# mcu_debug.net
KiCad netlist of a schematic drawn in Altium Designer
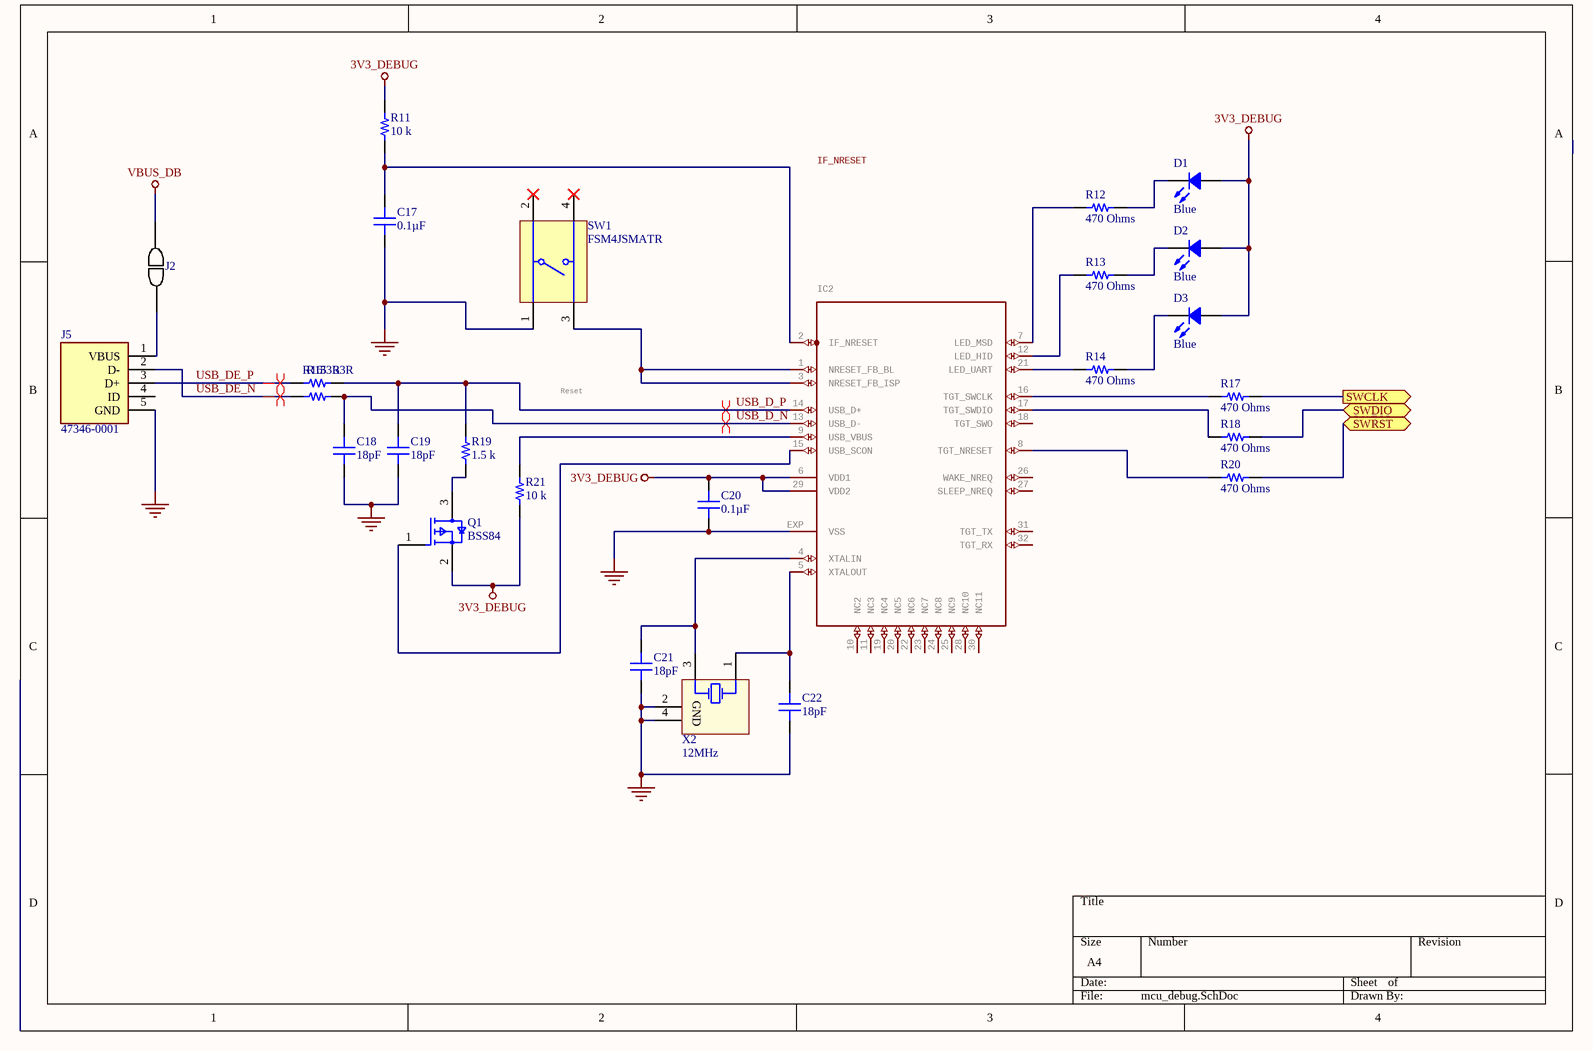
[diagram p0: mcu_debug.SchDoc]

(export (version "E")
  (design (tool "Eeschema 10.0.6"))
  (components
    (comp (ref "C17")
      (value "0.1µF")
      (footprint "CAP 0603_1608")
      (description "CAP CER 0.1UF 10V X7R 0603")
      (fields (field (name "PART NUMBER") "C0603T104K8RAC7867") (field (name "MANUFACTURER") "KEMET"))
      (libsource (lib "Celestial Altium Library - altium_library (2)") (part "Capacitor"))
    )
    (comp (ref "C18")
      (value "18pF")
      (footprint "CAP 0603_1608")
      (description "CAP CER 18PF 10V C0G/NP0 0603")
      (fields
        (field (name "PART NUMBER") "VJ0603A180FXQCW1BC")
        (field (name "MANUFACTURER") "Vishay Vitramon")
      )
      (libsource (lib "Celestial Altium Library - altium_library (2)") (part "Capacitor"))
    )
    (comp (ref "C19")
      (value "18pF")
      (footprint "CAP 0603_1608")
      (description "CAP CER 18PF 10V C0G/NP0 0603")
      (fields
        (field (name "PART NUMBER") "VJ0603A180FXQCW1BC")
        (field (name "MANUFACTURER") "Vishay Vitramon")
      )
      (libsource (lib "Celestial Altium Library - altium_library (2)") (part "Capacitor"))
    )
    (comp (ref "C20")
      (value "0.1µF")
      (footprint "CAP 0603_1608")
      (description "CAP CER 0.1UF 10V X7R 0603")
      (fields (field (name "PART NUMBER") "C0603T104K8RAC7867") (field (name "MANUFACTURER") "KEMET"))
      (libsource (lib "Celestial Altium Library - altium_library (2)") (part "Capacitor"))
    )
    (comp (ref "C21")
      (value "18pF")
      (footprint "CAP 0603_1608")
      (description "CAP CER 18PF 10V C0G/NP0 0603")
      (fields
        (field (name "PART NUMBER") "VJ0603A180FXQCW1BC")
        (field (name "MANUFACTURER") "Vishay Vitramon")
      )
      (libsource (lib "Celestial Altium Library - altium_library (2)") (part "Capacitor"))
    )
    (comp (ref "C22")
      (value "18pF")
      (footprint "CAP 0603_1608")
      (description "CAP CER 18PF 10V C0G/NP0 0603")
      (fields
        (field (name "PART NUMBER") "VJ0603A180FXQCW1BC")
        (field (name "MANUFACTURER") "Vishay Vitramon")
      )
      (libsource (lib "Celestial Altium Library - altium_library (2)") (part "Capacitor"))
    )
    (comp (ref "D1")
      (value "Blue")
      (footprint "LED 0603_1608 BLUE")
      (description "LED BLUE 0603 SMD")
      (fields
        (field (name "PART NUMBER") "VLMB1300-GS08")
        (field (name "MANUFACTURER") "Vishay Semiconductor Opto Division")
      )
      (libsource (lib "Celestial Altium Library - altium_library (2)") (part "LED"))
    )
    (comp (ref "D2")
      (value "Blue")
      (footprint "LED 0603_1608 BLUE")
      (description "LED BLUE 0603 SMD")
      (fields
        (field (name "PART NUMBER") "VLMB1300-GS08")
        (field (name "MANUFACTURER") "Vishay Semiconductor Opto Division")
      )
      (libsource (lib "Celestial Altium Library - altium_library (2)") (part "LED"))
    )
    (comp (ref "D3")
      (value "Blue")
      (footprint "LED 0603_1608 BLUE")
      (description "LED BLUE 0603 SMD")
      (fields
        (field (name "PART NUMBER") "VLMB1300-GS08")
        (field (name "MANUFACTURER") "Vishay Semiconductor Opto Division")
      )
      (libsource (lib "Celestial Altium Library - altium_library (2)") (part "LED"))
    )
    (comp (ref "IC2")
      (value "CMSIS-DAP Interface : 32-bit LPC11U00 ARM Cortex M3 RISC 64KB Flash 2.5V/3.3V 33-Pin HVQFN EP")
      (footprint "HVQFN33")
      (fields (field (name "MF") "NXP") (field (name "LIBRARYNAME") "mbed-HDK-MF-NXP"))
      (libsource (lib "mbed-HDK-MF-NXP") (part "IF_LPC11U35FHI33/501"))
    )
    (comp (ref "J2")
      (value "103185-2")
      (footprint "HDRV2W89P0X254_1X2_467X234X820P")
      (description "02 MODII HDR SRST B/A .100CL")
      (libsource (lib "103185-2") (part "103185-2"))
    )
    (comp (ref "J5")
      (value "47346-0001")
      (footprint "SamacSys:47346-0001")
      (description "Connector")
      (fields (field (name "MOUSER PART NUMBER") "538-47346-0001"))
      (libsource (lib "SamacSys") (part "47346-0001"))
    )
    (comp (ref "Q1")
      (value "BSS84")
      (footprint "FP-SOT23-MFG")
      (description "MOSFET P-CH 50V 130MA SOT-23")
      (fields
        (field (name "OCTOPART") "https://octopart.com/bss84%2C215-nexperia-78739375")
        (field (name "MANUFACTURER PART NUMBER") "BSS84,215")
      )
      (libsource (lib "Altium Content Vault") (part "2a9bca3c979204b206c86ddeb8c1a69"))
    )
    (comp (ref "R11")
      (value "10 k")
      (footprint "RES 0603_1608")
      (description "RES 10K OHM 0.1% 1/16W 0603")
      (fields
        (field (name "PART NUMBER") "RNCS0603BKE10K0")
        (field (name "MANUFACTURER") "Stackpole Electronics Inc")
      )
      (libsource (lib "Celestial Altium Library - altium_library (2)") (part "Resistor"))
    )
    (comp (ref "R12")
      (value "470 Ohms")
      (footprint "RES 0603_1608")
      (description "RES SMD 470 OHM 5% 1/4W 0603")
      (fields (field (name "PART NUMBER") "CRCW0603470RJNEAHP") (field (name "MANUFACTURER") "Vishay Dale"))
      (libsource (lib "Celestial Altium Library - altium_library (2)") (part "Resistor"))
    )
    (comp (ref "R13")
      (value "470 Ohms")
      (footprint "RES 0603_1608")
      (description "RES SMD 470 OHM 5% 1/4W 0603")
      (fields (field (name "PART NUMBER") "CRCW0603470RJNEAHP") (field (name "MANUFACTURER") "Vishay Dale"))
      (libsource (lib "Celestial Altium Library - altium_library (2)") (part "Resistor"))
    )
    (comp (ref "R14")
      (value "470 Ohms")
      (footprint "RES 0603_1608")
      (description "RES SMD 470 OHM 5% 1/4W 0603")
      (fields (field (name "PART NUMBER") "CRCW0603470RJNEAHP") (field (name "MANUFACTURER") "Vishay Dale"))
      (libsource (lib "Celestial Altium Library - altium_library (2)") (part "Resistor"))
    )
    (comp (ref "R15")
      (value "33R")
      (footprint "RES 0603_1608")
      (description "RES SMD 33 OHM 0.1% 1/16W 0603")
      (fields
        (field (name "PART NUMBER") "CPF0603B33RE")
        (field (name "MANUFACTURER") "TE Connectivity Passive Product")
      )
      (libsource (lib "Celestial Altium Library - altium_library (2)") (part "Resistor"))
    )
    (comp (ref "R16")
      (value "33R")
      (footprint "RES 0603_1608")
      (description "RES SMD 33 OHM 0.1% 1/16W 0603")
      (fields
        (field (name "PART NUMBER") "CPF0603B33RE")
        (field (name "MANUFACTURER") "TE Connectivity Passive Product")
      )
      (libsource (lib "Celestial Altium Library - altium_library (2)") (part "Resistor"))
    )
    (comp (ref "R17")
      (value "470 Ohms")
      (footprint "RES 0603_1608")
      (description "RES SMD 470 OHM 5% 1/4W 0603")
      (fields (field (name "PART NUMBER") "CRCW0603470RJNEAHP") (field (name "MANUFACTURER") "Vishay Dale"))
      (libsource (lib "Celestial Altium Library - altium_library (2)") (part "Resistor"))
    )
    (comp (ref "R18")
      (value "470 Ohms")
      (footprint "RES 0603_1608")
      (description "RES SMD 470 OHM 5% 1/4W 0603")
      (fields (field (name "PART NUMBER") "CRCW0603470RJNEAHP") (field (name "MANUFACTURER") "Vishay Dale"))
      (libsource (lib "Celestial Altium Library - altium_library (2)") (part "Resistor"))
    )
    (comp (ref "R19")
      (value "1.5 k")
      (footprint "RES 0603_1608")
      (description "CRGP 0603 1K5 1%")
      (fields
        (field (name "PART NUMBER") "CRGP0603F1K5")
        (field (name "MANUFACTURER") "TE Connectivity Passive Product")
      )
      (libsource (lib "Celestial Altium Library - altium_library (2)") (part "Resistor"))
    )
    (comp (ref "R20")
      (value "470 Ohms")
      (footprint "RES 0603_1608")
      (description "RES SMD 470 OHM 5% 1/4W 0603")
      (fields (field (name "PART NUMBER") "CRCW0603470RJNEAHP") (field (name "MANUFACTURER") "Vishay Dale"))
      (libsource (lib "Celestial Altium Library - altium_library (2)") (part "Resistor"))
    )
    (comp (ref "R21")
      (value "10 k")
      (footprint "RES 0603_1608")
      (description "RES 10K OHM 0.1% 1/16W 0603")
      (fields
        (field (name "PART NUMBER") "RNCS0603BKE10K0")
        (field (name "MANUFACTURER") "Stackpole Electronics Inc")
      )
      (libsource (lib "Celestial Altium Library - altium_library (2)") (part "Resistor"))
    )
    (comp (ref "SW1")
      (value "FSM4JSMATR")
      (footprint "TECO-FSM4JSMATR_V")
      (description "Micro Miniature Push Button Switch FSM JSM, 50 mA, -35 to 85 degC, 4-Pin SMD, RoHS, Tape and Reel")
      (fields (field (name "MANUFACTURER") "TE Connectivity"))
      (libsource (lib "Altium Content Vault") (part "SW-SPST-4_A"))
    )
    (comp (ref "X2")
      (value "12MHz")
      (footprint "ABRA-ABMM2-4_V")
      (fields (field (name "MANUFACTURER") "Abracon") (field (name "PARTNUMBER") "ABMM2-8.000MHZ-E2-T"))
      (libsource (lib "Altium Content Vault") (part "ABRA-XTAL_1-3-4"))
    )
  )
  (nets
    (net (code "2") (name "/SWCLK") (class "Default")
      (node (ref "R17") (pin "2") (pinfunction "2_2") (pintype "passive"))
    )
    (net (code "3") (name "/SWDIO") (class "Default")
      (node (ref "R18") (pin "2") (pinfunction "2_2") (pintype "passive"))
    )
    (net (code "4") (name "/SWRST") (class "Default")
      (node (ref "R20") (pin "2") (pinfunction "2_2") (pintype "passive"))
    )
    (net (code "5") (name "/USB_DE_N") (class "Default")
      (node (ref "J5") (pin "2") (pinfunction "D-_2") (pintype "passive"))
      (node (ref "R15") (pin "1") (pinfunction "1_1") (pintype "passive"))
    )
    (net (code "6") (name "/USB_DE_P") (class "Default")
      (node (ref "J5") (pin "3") (pinfunction "D+_3") (pintype "passive"))
      (node (ref "R16") (pin "1") (pinfunction "1_1") (pintype "passive"))
    )
    (net (code "7") (name "/USB_D_N") (class "Default")
      (node (ref "C18") (pin "2") (pinfunction "2_2") (pintype "passive"))
      (node (ref "IC2") (pin "13") (pinfunction "USB_D-_13") (pintype "bidirectional"))
      (node (ref "R15") (pin "2") (pinfunction "2_2") (pintype "passive"))
    )
    (net (code "8") (name "/USB_D_P") (class "Default")
      (node (ref "C19") (pin "2") (pinfunction "2_2") (pintype "passive"))
      (node (ref "IC2") (pin "14") (pinfunction "USB_D+_14") (pintype "bidirectional"))
      (node (ref "R16") (pin "2") (pinfunction "2_2") (pintype "passive"))
      (node (ref "R19") (pin "2") (pinfunction "2_2") (pintype "passive"))
    )
    (net (code "9") (name "3V3_DEBUG") (class "Default")
      (node (ref "C20") (pin "2") (pinfunction "2_2") (pintype "passive"))
      (node (ref "D1") (pin "1") (pinfunction "1_1") (pintype "passive"))
      (node (ref "D2") (pin "1") (pinfunction "1_1") (pintype "passive"))
      (node (ref "D3") (pin "1") (pinfunction "1_1") (pintype "passive"))
      (node (ref "IC2") (pin "29") (pinfunction "VDD2_29") (pintype "power_in"))
      (node (ref "IC2") (pin "6") (pinfunction "VDD1_6") (pintype "power_in"))
      (node (ref "Q1") (pin "2") (pinfunction "S_2") (pintype "passive"))
      (node (ref "R11") (pin "2") (pinfunction "2_2") (pintype "passive"))
      (node (ref "R21") (pin "1") (pinfunction "1_1") (pintype "passive"))
    )
    (net (code "10") (name "GND") (class "Default")
      (node (ref "C17") (pin "1") (pinfunction "1_1") (pintype "passive"))
      (node (ref "C18") (pin "1") (pinfunction "1_1") (pintype "passive"))
      (node (ref "C19") (pin "1") (pinfunction "1_1") (pintype "passive"))
      (node (ref "C20") (pin "1") (pinfunction "1_1") (pintype "passive"))
      (node (ref "C21") (pin "1") (pinfunction "1_1") (pintype "passive"))
      (node (ref "C22") (pin "1") (pinfunction "1_1") (pintype "passive"))
      (node (ref "IC2") (pin "EXP") (pinfunction "VSS_EXP") (pintype "power_in"))
      (node (ref "J5") (pin "5") (pinfunction "GND_5") (pintype "passive"))
      (node (ref "SW1") (pin "1") (pinfunction "1_1") (pintype "passive"))
      (node (ref "X2") (pin "2") (pinfunction "GND_2") (pintype "power_in"))
      (node (ref "X2") (pin "4") (pinfunction "GND_4") (pintype "power_in"))
    )
    (net (code "11") (name "Net-(D1-Pad2)") (class "Default")
      (node (ref "D1") (pin "2") (pinfunction "2_2") (pintype "passive"))
      (node (ref "R12") (pin "2") (pinfunction "2_2") (pintype "passive"))
    )
    (net (code "12") (name "Net-(D2-Pad2)") (class "Default")
      (node (ref "D2") (pin "2") (pinfunction "2_2") (pintype "passive"))
      (node (ref "R13") (pin "2") (pinfunction "2_2") (pintype "passive"))
    )
    (net (code "13") (name "Net-(D3-Pad2)") (class "Default")
      (node (ref "D3") (pin "2") (pinfunction "2_2") (pintype "passive"))
      (node (ref "R14") (pin "2") (pinfunction "2_2") (pintype "passive"))
    )
    (net (code "14") (name "Net-(IC2-IF_NRESET)") (class "Default")
      (node (ref "C17") (pin "2") (pinfunction "2_2") (pintype "passive"))
      (node (ref "IC2") (pin "2") (pinfunction "IF_NRESET_2") (pintype "bidirectional"))
      (node (ref "R11") (pin "1") (pinfunction "1_1") (pintype "passive"))
    )
    (net (code "15") (name "Net-(IC2-LED_HID)") (class "Default")
      (node (ref "IC2") (pin "12") (pinfunction "LED_HID_12") (pintype "bidirectional"))
      (node (ref "R13") (pin "1") (pinfunction "1_1") (pintype "passive"))
    )
    (net (code "16") (name "Net-(IC2-LED_MSD)") (class "Default")
      (node (ref "IC2") (pin "7") (pinfunction "LED_MSD_7") (pintype "bidirectional"))
      (node (ref "R12") (pin "1") (pinfunction "1_1") (pintype "passive"))
    )
    (net (code "17") (name "Net-(IC2-LED_UART)") (class "Default")
      (node (ref "IC2") (pin "21") (pinfunction "LED_UART_21") (pintype "bidirectional"))
      (node (ref "R14") (pin "1") (pinfunction "1_1") (pintype "passive"))
    )
    (net (code "18") (name "Net-(IC2-NRESET_FB_BL)") (class "Default")
      (node (ref "IC2") (pin "1") (pinfunction "NRESET_FB_BL_1") (pintype "bidirectional"))
      (node (ref "IC2") (pin "3") (pinfunction "NRESET_FB_ISP_3") (pintype "bidirectional"))
      (node (ref "SW1") (pin "3") (pinfunction "3_3") (pintype "passive"))
    )
    (net (code "19") (name "Net-(IC2-TGT_NRESET)") (class "Default")
      (node (ref "IC2") (pin "8") (pinfunction "TGT_NRESET_8") (pintype "bidirectional"))
      (node (ref "R20") (pin "1") (pinfunction "1_1") (pintype "passive"))
    )
    (net (code "20") (name "Net-(IC2-TGT_SWCLK)") (class "Default")
      (node (ref "IC2") (pin "16") (pinfunction "TGT_SWCLK_16") (pintype "bidirectional"))
      (node (ref "R17") (pin "1") (pinfunction "1_1") (pintype "passive"))
    )
    (net (code "21") (name "Net-(IC2-TGT_SWDIO)") (class "Default")
      (node (ref "IC2") (pin "17") (pinfunction "TGT_SWDIO_17") (pintype "bidirectional"))
      (node (ref "R18") (pin "1") (pinfunction "1_1") (pintype "passive"))
    )
    (net (code "22") (name "Net-(IC2-USB_SCON)") (class "Default")
      (node (ref "IC2") (pin "15") (pinfunction "USB_SCON_15") (pintype "bidirectional"))
      (node (ref "Q1") (pin "1") (pinfunction "G_1") (pintype "passive"))
    )
    (net (code "23") (name "Net-(IC2-USB_VBUS)") (class "Default")
      (node (ref "IC2") (pin "9") (pinfunction "USB_VBUS_9") (pintype "bidirectional"))
      (node (ref "R21") (pin "2") (pinfunction "2_2") (pintype "passive"))
    )
    (net (code "24") (name "Net-(IC2-XTALIN)") (class "Default")
      (node (ref "C21") (pin "2") (pinfunction "2_2") (pintype "passive"))
      (node (ref "IC2") (pin "4") (pinfunction "XTALIN_4") (pintype "bidirectional"))
      (node (ref "X2") (pin "3") (pinfunction "X2_3") (pintype "passive"))
    )
    (net (code "25") (name "Net-(IC2-XTALOUT)") (class "Default")
      (node (ref "C22") (pin "2") (pinfunction "2_2") (pintype "passive"))
      (node (ref "IC2") (pin "5") (pinfunction "XTALOUT_5") (pintype "bidirectional"))
      (node (ref "X2") (pin "1") (pinfunction "X1_1") (pintype "passive"))
    )
    (net (code "26") (name "Net-(J5-VBUS)") (class "Default")
      (node (ref "J2") (pin "2") (pinfunction "2_2") (pintype "passive"))
      (node (ref "J5") (pin "1") (pinfunction "VBUS_1") (pintype "passive"))
    )
    (net (code "27") (name "Net-(Q1-D)") (class "Default")
      (node (ref "Q1") (pin "3") (pinfunction "D_3") (pintype "passive"))
      (node (ref "R19") (pin "1") (pinfunction "1_1") (pintype "passive"))
    )
    (net (code "28") (name "VBUS_DB") (class "Default")
      (node (ref "J2") (pin "1") (pinfunction "1_1") (pintype "passive"))
    )
    (net (code "29") (name "unconnected-(IC2-NC2-Pad10)") (class "Default")
      (node (ref "IC2") (pin "10") (pinfunction "NC2_10") (pintype "bidirectional"))
    )
    (net (code "30") (name "unconnected-(IC2-NC3-Pad11)") (class "Default")
      (node (ref "IC2") (pin "11") (pinfunction "NC3_11") (pintype "bidirectional"))
    )
    (net (code "31") (name "unconnected-(IC2-NC4-Pad19)") (class "Default")
      (node (ref "IC2") (pin "19") (pinfunction "NC4_19") (pintype "bidirectional"))
    )
    (net (code "32") (name "unconnected-(IC2-NC5-Pad20)") (class "Default")
      (node (ref "IC2") (pin "20") (pinfunction "NC5_20") (pintype "bidirectional"))
    )
    (net (code "33") (name "unconnected-(IC2-NC6-Pad22)") (class "Default")
      (node (ref "IC2") (pin "22") (pinfunction "NC6_22") (pintype "bidirectional"))
    )
    (net (code "34") (name "unconnected-(IC2-NC7-Pad23)") (class "Default")
      (node (ref "IC2") (pin "23") (pinfunction "NC7_23") (pintype "bidirectional"))
    )
    (net (code "35") (name "unconnected-(IC2-NC8-Pad24)") (class "Default")
      (node (ref "IC2") (pin "24") (pinfunction "NC8_24") (pintype "bidirectional"))
    )
    (net (code "36") (name "unconnected-(IC2-NC9-Pad25)") (class "Default")
      (node (ref "IC2") (pin "25") (pinfunction "NC9_25") (pintype "bidirectional"))
    )
    (net (code "37") (name "unconnected-(IC2-NC10-Pad28)") (class "Default")
      (node (ref "IC2") (pin "28") (pinfunction "NC10_28") (pintype "bidirectional"))
    )
    (net (code "38") (name "unconnected-(IC2-NC11-Pad30)") (class "Default")
      (node (ref "IC2") (pin "30") (pinfunction "NC11_30") (pintype "bidirectional"))
    )
    (net (code "39") (name "unconnected-(IC2-SLEEP_NREQ-Pad27)") (class "Default")
      (node (ref "IC2") (pin "27") (pinfunction "SLEEP_NREQ_27") (pintype "bidirectional"))
    )
    (net (code "40") (name "unconnected-(IC2-TGT_RX-Pad32)") (class "Default")
      (node (ref "IC2") (pin "32") (pinfunction "TGT_RX_32") (pintype "bidirectional"))
    )
    (net (code "41") (name "unconnected-(IC2-TGT_SWO-Pad18)") (class "Default")
      (node (ref "IC2") (pin "18") (pinfunction "TGT_SWO_18") (pintype "bidirectional"))
    )
    (net (code "42") (name "unconnected-(IC2-TGT_TX-Pad31)") (class "Default")
      (node (ref "IC2") (pin "31") (pinfunction "TGT_TX_31") (pintype "bidirectional"))
    )
    (net (code "43") (name "unconnected-(IC2-WAKE_NREQ-Pad26)") (class "Default")
      (node (ref "IC2") (pin "26") (pinfunction "WAKE_NREQ_26") (pintype "bidirectional"))
    )
    (net (code "44") (name "unconnected-(J5-ID-Pad4)") (class "Default")
      (node (ref "J5") (pin "4") (pinfunction "ID_4") (pintype "passive"))
    )
    (net (code "45") (name "unconnected-(SW1-Pad2)") (class "Default")
      (node (ref "SW1") (pin "2") (pinfunction "2_2") (pintype "passive+no_connect"))
    )
    (net (code "46") (name "unconnected-(SW1-Pad4)") (class "Default")
      (node (ref "SW1") (pin "4") (pinfunction "4_4") (pintype "passive+no_connect"))
    )
  )
)
